# Nano_Isp.net
KiCad netlist of a schematic drawn in EAGLE
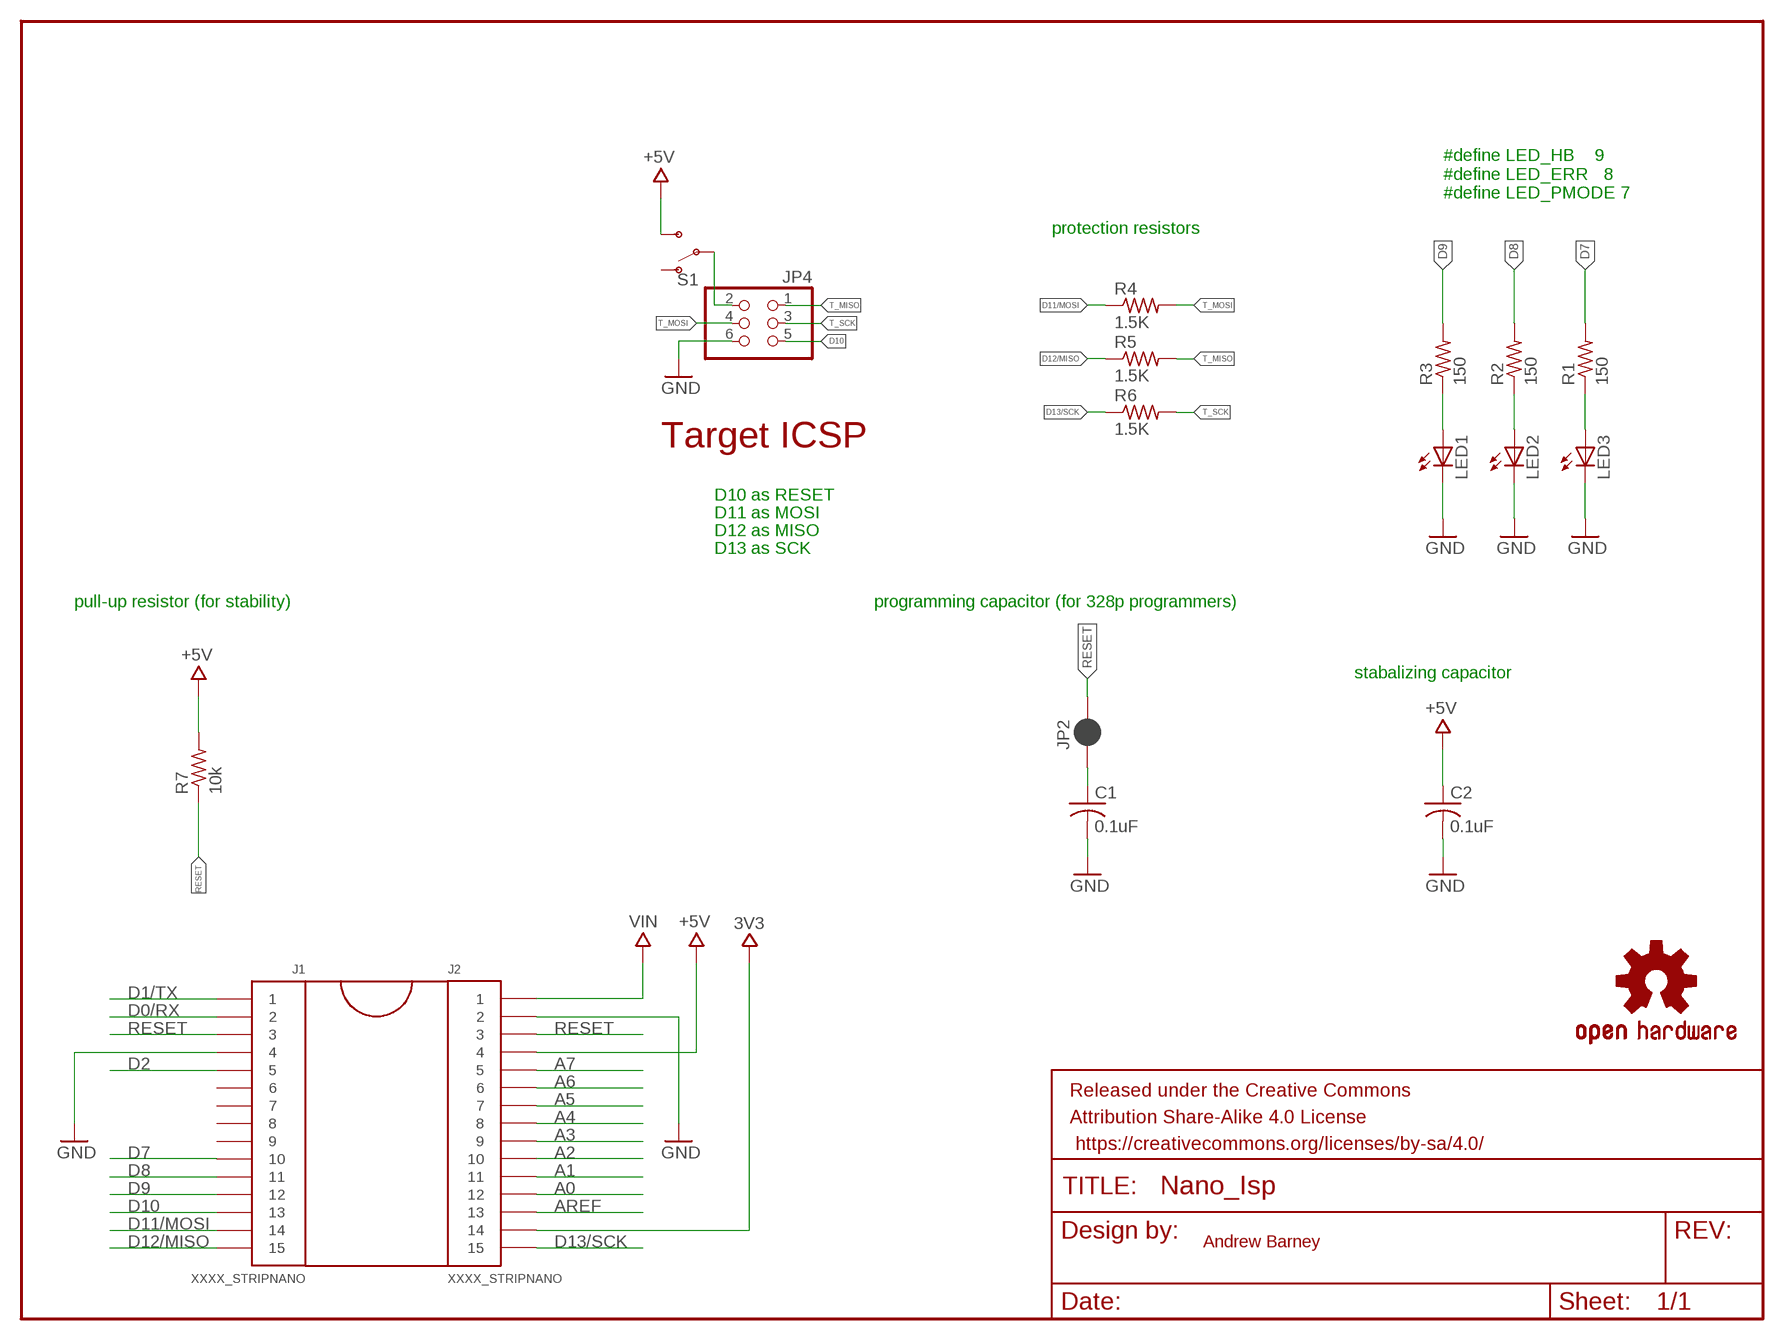
[diagram p0: schematic, sheet 1]

(export (version "E")
  (design (tool "Eeschema 10.0.6"))
  (components
    (comp (ref "C1")
      (value "0.1uF")
      (footprint "eagle-import:C0805")
      (libsource (lib "eagle-import") (part "C-USC0805"))
    )
    (comp (ref "C2")
      (value "0.1uF")
      (footprint "eagle-import:C0805")
      (libsource (lib "eagle-import") (part "C-USC0805"))
    )
    (comp (ref "FRAME1")
      (value "FRAME-LETTERNO_PACKAGE")
      (footprint "eagle-import:DUMMY")
      (fields (field (name "DESIGNER") "Nobody"))
      (libsource (lib "eagle-import") (part "FRAME-LETTERNO_PACKAGE"))
    )
    (comp (ref "J1")
      (value "XXXX_STRIPNANO")
      (footprint "eagle-import:HEAD15-NOSS")
      (libsource (lib "eagle-import") (part "XXXX_STRIPNANO"))
    )
    (comp (ref "J2")
      (value "XXXX_STRIPNANO")
      (footprint "eagle-import:HEAD15-NOSS")
      (libsource (lib "eagle-import") (part "XXXX_STRIPNANO"))
    )
    (comp (ref "JP2")
      (value "JUMPER-SMT_2_NC_PASTE_SILK")
      (footprint "eagle-import:SMT-JUMPER_2_NC_PASTE_SILK")
      (libsource (lib "eagle-import") (part "JUMPER-SMT_2_NC_PASTE_SILK"))
    )
    (comp (ref "JP4")
      (value "PINHD-2X3")
      (footprint "eagle-import:2X03")
      (libsource (lib "eagle-import") (part "PINHD-2X3"))
    )
    (comp (ref "LED1")
      (value "LEDCHIP-LED0805")
      (footprint "eagle-import:CHIP-LED0805")
      (libsource (lib "eagle-import") (part "LEDCHIP-LED0805"))
    )
    (comp (ref "LED2")
      (value "LEDCHIP-LED0805")
      (footprint "eagle-import:CHIP-LED0805")
      (libsource (lib "eagle-import") (part "LEDCHIP-LED0805"))
    )
    (comp (ref "LED3")
      (value "LEDCHIP-LED0805")
      (footprint "eagle-import:CHIP-LED0805")
      (libsource (lib "eagle-import") (part "LEDCHIP-LED0805"))
    )
    (comp (ref "R1")
      (value "150")
      (footprint "eagle-import:R0805")
      (libsource (lib "eagle-import") (part "R-US_R0805"))
    )
    (comp (ref "R2")
      (value "150")
      (footprint "eagle-import:R0805")
      (libsource (lib "eagle-import") (part "R-US_R0805"))
    )
    (comp (ref "R3")
      (value "150")
      (footprint "eagle-import:R0805")
      (libsource (lib "eagle-import") (part "R-US_R0805"))
    )
    (comp (ref "R4")
      (value "1.5K")
      (footprint "eagle-import:R0805")
      (libsource (lib "eagle-import") (part "R-US_R0805"))
    )
    (comp (ref "R5")
      (value "1.5K")
      (footprint "eagle-import:R0805")
      (libsource (lib "eagle-import") (part "R-US_R0805"))
    )
    (comp (ref "R6")
      (value "1.5K")
      (footprint "eagle-import:R0805")
      (libsource (lib "eagle-import") (part "R-US_R0805"))
    )
    (comp (ref "R7")
      (value "10k")
      (footprint "eagle-import:R0805")
      (libsource (lib "eagle-import") (part "R-US_R0805"))
    )
    (comp (ref "S1")
      (value "SWITCH-SPDT-SMD-AYZ0202")
      (footprint "eagle-import:SWITCH_DPDT_SMD_AYZ0202")
      (libsource (lib "eagle-import") (part "SWITCH-SPDT-SMD-AYZ0202"))
    )
    (comp (ref "U$9")
      (value "OSHW-LOGOS")
      (footprint "eagle-import:OSHW-LOGO-S")
      (libsource (lib "eagle-import") (part "OSHW-LOGOS"))
    )
  )
  (nets
    (net (code "1") (name "+5V") (class "Default")
      (node (ref "C2") (pin "1") (pinfunction "1_1") (pintype "passive"))
      (node (ref "J2") (pin "4") (pinfunction "4_4") (pintype "passive"))
      (node (ref "R7") (pin "2") (pinfunction "2_2") (pintype "passive"))
      (node (ref "S1") (pin "3") (pinfunction "S_3") (pintype "passive"))
    )
    (net (code "2") (name "/A0") (class "Default")
      (node (ref "J2") (pin "12") (pinfunction "12_12") (pintype "passive"))
    )
    (net (code "3") (name "/A1") (class "Default")
      (node (ref "J2") (pin "11") (pinfunction "11_11") (pintype "passive"))
    )
    (net (code "4") (name "/A2") (class "Default")
      (node (ref "J2") (pin "10") (pinfunction "10_10") (pintype "passive"))
    )
    (net (code "5") (name "/A3") (class "Default")
      (node (ref "J2") (pin "9") (pinfunction "9_9") (pintype "passive"))
    )
    (net (code "6") (name "/A4") (class "Default")
      (node (ref "J2") (pin "8") (pinfunction "8_8") (pintype "passive"))
    )
    (net (code "7") (name "/A5") (class "Default")
      (node (ref "J2") (pin "7") (pinfunction "7_7") (pintype "passive"))
    )
    (net (code "8") (name "/A6") (class "Default")
      (node (ref "J2") (pin "6") (pinfunction "6_6") (pintype "passive"))
    )
    (net (code "9") (name "/A7") (class "Default")
      (node (ref "J2") (pin "5") (pinfunction "5_5") (pintype "passive"))
    )
    (net (code "10") (name "/AREF") (class "Default")
      (node (ref "J2") (pin "13") (pinfunction "13_13") (pintype "passive"))
    )
    (net (code "11") (name "/D0{slash}RX") (class "Default")
      (node (ref "J1") (pin "2") (pinfunction "2_2") (pintype "passive"))
    )
    (net (code "12") (name "/D1{slash}TX") (class "Default")
      (node (ref "J1") (pin "1") (pinfunction "1_1") (pintype "passive"))
    )
    (net (code "13") (name "/D2") (class "Default")
      (node (ref "J1") (pin "5") (pinfunction "5_5") (pintype "passive"))
    )
    (net (code "14") (name "3V3") (class "Default")
      (node (ref "J2") (pin "14") (pinfunction "14_14") (pintype "passive"))
    )
    (net (code "15") (name "D7") (class "Default")
      (node (ref "J1") (pin "10") (pinfunction "10_10") (pintype "passive"))
      (node (ref "R1") (pin "2") (pinfunction "2_2") (pintype "passive"))
    )
    (net (code "16") (name "D8") (class "Default")
      (node (ref "J1") (pin "11") (pinfunction "11_11") (pintype "passive"))
      (node (ref "R2") (pin "2") (pinfunction "2_2") (pintype "passive"))
    )
    (net (code "17") (name "D9") (class "Default")
      (node (ref "J1") (pin "12") (pinfunction "12_12") (pintype "passive"))
      (node (ref "R3") (pin "2") (pinfunction "2_2") (pintype "passive"))
    )
    (net (code "18") (name "D10") (class "Default")
      (node (ref "J1") (pin "13") (pinfunction "13_13") (pintype "passive"))
      (node (ref "JP4") (pin "5") (pinfunction "5_5") (pintype "passive"))
    )
    (net (code "19") (name "D11{slash}MOSI") (class "Default")
      (node (ref "J1") (pin "14") (pinfunction "14_14") (pintype "passive"))
      (node (ref "R4") (pin "1") (pinfunction "1_1") (pintype "passive"))
    )
    (net (code "20") (name "D12{slash}MISO") (class "Default")
      (node (ref "J1") (pin "15") (pinfunction "15_15") (pintype "passive"))
      (node (ref "R5") (pin "1") (pinfunction "1_1") (pintype "passive"))
    )
    (net (code "21") (name "D13{slash}SCK") (class "Default")
      (node (ref "J2") (pin "15") (pinfunction "15_15") (pintype "passive"))
      (node (ref "R6") (pin "1") (pinfunction "1_1") (pintype "passive"))
    )
    (net (code "22") (name "GND") (class "Default")
      (node (ref "C1") (pin "2") (pinfunction "2_2") (pintype "passive"))
      (node (ref "C2") (pin "2") (pinfunction "2_2") (pintype "passive"))
      (node (ref "J1") (pin "4") (pinfunction "4_4") (pintype "passive"))
      (node (ref "J2") (pin "2") (pinfunction "2_2") (pintype "passive"))
      (node (ref "JP4") (pin "6") (pinfunction "6_6") (pintype "passive"))
      (node (ref "LED1") (pin "C") (pinfunction "C_C") (pintype "passive"))
      (node (ref "LED2") (pin "C") (pinfunction "C_C") (pintype "passive"))
      (node (ref "LED3") (pin "C") (pinfunction "C_C") (pintype "passive"))
    )
    (net (code "23") (name "Net-(C1-Pad1)") (class "Default")
      (node (ref "C1") (pin "1") (pinfunction "1_1") (pintype "passive"))
      (node (ref "JP2") (pin "1") (pinfunction "1_1") (pintype "passive"))
    )
    (net (code "24") (name "Net-(LED1-PadA)") (class "Default")
      (node (ref "LED1") (pin "A") (pinfunction "A_A") (pintype "passive"))
      (node (ref "R3") (pin "1") (pinfunction "1_1") (pintype "passive"))
    )
    (net (code "25") (name "Net-(LED2-PadA)") (class "Default")
      (node (ref "LED2") (pin "A") (pinfunction "A_A") (pintype "passive"))
      (node (ref "R2") (pin "1") (pinfunction "1_1") (pintype "passive"))
    )
    (net (code "26") (name "Net-(LED3-PadA)") (class "Default")
      (node (ref "LED3") (pin "A") (pinfunction "A_A") (pintype "passive"))
      (node (ref "R1") (pin "1") (pinfunction "1_1") (pintype "passive"))
    )
    (net (code "27") (name "Net-(S1-P)") (class "Default")
      (node (ref "JP4") (pin "2") (pinfunction "2_2") (pintype "passive"))
      (node (ref "S1") (pin "2") (pinfunction "P_2") (pintype "passive"))
    )
    (net (code "28") (name "RESET") (class "Default")
      (node (ref "J1") (pin "3") (pinfunction "3_3") (pintype "passive"))
      (node (ref "J2") (pin "3") (pinfunction "3_3") (pintype "passive"))
      (node (ref "JP2") (pin "2") (pinfunction "2_2") (pintype "passive"))
      (node (ref "R7") (pin "1") (pinfunction "1_1") (pintype "passive"))
    )
    (net (code "29") (name "T_MISO") (class "Default")
      (node (ref "JP4") (pin "1") (pinfunction "1_1") (pintype "passive"))
      (node (ref "R5") (pin "2") (pinfunction "2_2") (pintype "passive"))
    )
    (net (code "30") (name "T_MOSI") (class "Default")
      (node (ref "JP4") (pin "4") (pinfunction "4_4") (pintype "passive"))
      (node (ref "R4") (pin "2") (pinfunction "2_2") (pintype "passive"))
    )
    (net (code "31") (name "T_SCK") (class "Default")
      (node (ref "JP4") (pin "3") (pinfunction "3_3") (pintype "passive"))
      (node (ref "R6") (pin "2") (pinfunction "2_2") (pintype "passive"))
    )
    (net (code "32") (name "VIN") (class "Default")
      (node (ref "J2") (pin "1") (pinfunction "1_1") (pintype "passive"))
    )
    (net (code "33") (name "unconnected-(J1-Pad6)") (class "Default")
      (node (ref "J1") (pin "6") (pinfunction "6_6") (pintype "passive"))
    )
    (net (code "34") (name "unconnected-(J1-Pad7)") (class "Default")
      (node (ref "J1") (pin "7") (pinfunction "7_7") (pintype "passive"))
    )
    (net (code "35") (name "unconnected-(J1-Pad8)") (class "Default")
      (node (ref "J1") (pin "8") (pinfunction "8_8") (pintype "passive"))
    )
    (net (code "36") (name "unconnected-(J1-Pad9)") (class "Default")
      (node (ref "J1") (pin "9") (pinfunction "9_9") (pintype "passive"))
    )
    (net (code "37") (name "unconnected-(S1-O-Pad1)") (class "Default")
      (node (ref "S1") (pin "1") (pinfunction "O_1") (pintype "passive"))
    )
  )
)
